# Reefing-PSU.net
KiCad netlist of a schematic drawn in Altium Designer
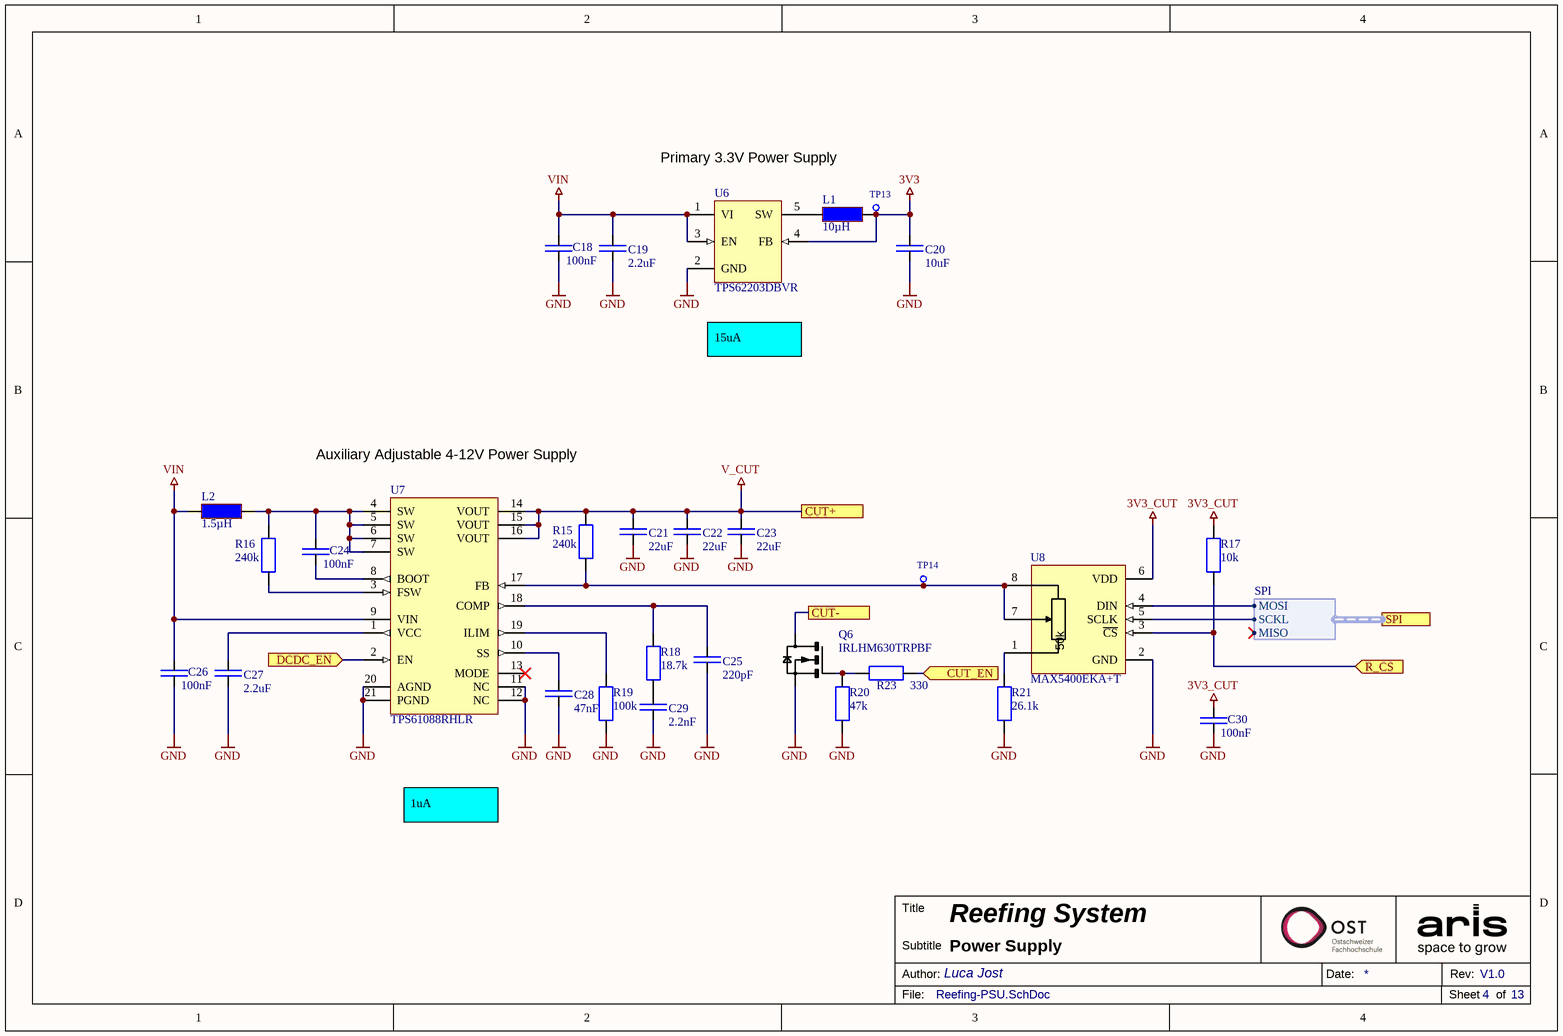
[diagram p0: Reefing-PSU.SchDoc]

(export (version "E")
  (design (tool "Eeschema 10.0.6"))
  (components
    (comp (ref "C18")
      (value "100nF")
      (footprint "SMD Keramikkondensator 0402")
      (description "SMD Ceramic Capacitor E6")
      (libsource (lib "Ceramic Capacitors-E6") (part "E6 - 100nF"))
    )
    (comp (ref "C19")
      (value "2.2uF")
      (footprint "SMD Keramikkondensator 0402")
      (description "SMD Ceramic Capacitor E6")
      (libsource (lib "Ceramic Capacitors-E6") (part "E6 - 2.2uF"))
    )
    (comp (ref "C20")
      (value "10uF")
      (footprint "SMD Keramikkondensator 0603")
      (description "SMD Ceramic Capacitor E6")
      (libsource (lib "Ceramic Capacitors-E6") (part "E6 - 10uF"))
    )
    (comp (ref "C21")
      (value "22uF")
      (footprint "SMD Keramikkondensator 0805")
      (description "SMD Ceramic Capacitor E6")
      (libsource (lib "Ceramic Capacitors-E6") (part "E6 - 22uF"))
    )
    (comp (ref "C22")
      (value "22uF")
      (footprint "SMD Keramikkondensator 0805")
      (description "SMD Ceramic Capacitor E6")
      (libsource (lib "Ceramic Capacitors-E6") (part "E6 - 22uF"))
    )
    (comp (ref "C23")
      (value "22uF")
      (footprint "SMD Keramikkondensator 0805")
      (description "SMD Ceramic Capacitor E6")
      (libsource (lib "Ceramic Capacitors-E6") (part "E6 - 22uF"))
    )
    (comp (ref "C24")
      (value "100nF")
      (footprint "SMD Keramikkondensator 0402")
      (description "SMD Ceramic Capacitor E6")
      (libsource (lib "Ceramic Capacitors-E6") (part "E6 - 100nF"))
    )
    (comp (ref "C25")
      (value "220pF")
      (footprint "SMD Keramikkondensator 0402")
      (description "SMD Ceramic Capacitor E6")
      (libsource (lib "Ceramic Capacitors-E6") (part "E6 - 220pF"))
    )
    (comp (ref "C26")
      (value "100nF")
      (footprint "SMD Keramikkondensator 0402")
      (description "SMD Ceramic Capacitor E6")
      (libsource (lib "Ceramic Capacitors-E6") (part "E6 - 100nF"))
    )
    (comp (ref "C27")
      (value "2.2uF")
      (footprint "SMD Keramikkondensator 0402")
      (description "SMD Ceramic Capacitor E6")
      (libsource (lib "Ceramic Capacitors-E6") (part "E6 - 2.2uF"))
    )
    (comp (ref "C28")
      (value "47nF")
      (footprint "SMD Keramikkondensator 0402")
      (description "SMD Ceramic Capacitor E6")
      (libsource (lib "Ceramic Capacitors-E6") (part "E6 - 47nF"))
    )
    (comp (ref "C29")
      (value "2.2nF")
      (footprint "SMD Keramikkondensator 0402")
      (description "SMD Ceramic Capacitor E6")
      (libsource (lib "Ceramic Capacitors-E6") (part "E6 - 2.2nF"))
    )
    (comp (ref "C30")
      (value "100nF")
      (footprint "SMD Keramikkondensator 0402")
      (description "SMD Ceramic Capacitor E6")
      (libsource (lib "Ceramic Capacitors-E6") (part "E6 - 100nF"))
    )
    (comp (ref "L1")
      (value "10µH")
      (footprint "SMD Inductor 4x4x1.8")
      (description "165mOhm SMD, 1.6A")
      (libsource (lib "Inductors") (part "Inductor 10µH / 1.6A"))
    )
    (comp (ref "L2")
      (value "1.5µH")
      (footprint "SMD Inductor 7.1x6.6")
      (description "8.5mΩ SMD, 7.1x6.6x5mm")
      (libsource (lib "Inductors") (part "Inductor 1.5µH / 10A"))
    )
    (comp (ref "Q6")
      (value "IRLHM630TRPBF")
      (footprint "SMD MOSFET DFN 3.3x3.3")
      (description "N-Channel 30V 21A 3.5mOhm@4.5V")
      (libsource (lib "Reefing System") (part "IRLHM630TRPBF"))
    )
    (comp (ref "R15")
      (value "240k")
      (footprint "SMD Widerstand 0402")
      (description "SMD Chip Resistor E24")
      (libsource (lib "Resistors-E24") (part "E24 - 240k"))
    )
    (comp (ref "R16")
      (value "240k")
      (footprint "SMD Widerstand 0402")
      (description "SMD Chip Resistor E24")
      (libsource (lib "Resistors-E24") (part "E24 - 240k"))
    )
    (comp (ref "R17")
      (value "10k")
      (footprint "SMD Widerstand 0402")
      (description "SMD Chip Resistor E24")
      (libsource (lib "Resistors-E24") (part "E24 - 10k"))
    )
    (comp (ref "R18")
      (value "18.7k")
      (footprint "SMD Widerstand 0402")
      (description "SMD Chip Resistor E96")
      (libsource (lib "Resistors-E96") (part "E96 - 18.7k"))
    )
    (comp (ref "R19")
      (value "100k")
      (footprint "SMD Widerstand 0402")
      (description "SMD Chip Resistor E24")
      (libsource (lib "Resistors-E24") (part "E24 - 100k"))
    )
    (comp (ref "R20")
      (value "47k")
      (footprint "SMD Widerstand 0402")
      (description "SMD Chip Resistor E24")
      (libsource (lib "Resistors-E24") (part "E24 - 47k"))
    )
    (comp (ref "R21")
      (value "26.1k")
      (footprint "SMD Widerstand 0402")
      (description "SMD Chip Resistor E96")
      (libsource (lib "Resistors-E96") (part "E96 - 26.1k"))
    )
    (comp (ref "R23")
      (value "330")
      (footprint "SMD Widerstand 0402")
      (description "SMD Chip Resistor E24")
      (libsource (lib "Resistors-E24") (part "E24 - 330"))
    )
    (comp (ref "TP13")
      (value "X-TP")
      (footprint "SMD Testpoint 1mm")
      (description "Testpunkt")
      (libsource (lib "Fleet-Monitor") (part "X-TP"))
    )
    (comp (ref "TP14")
      (value "X-TP")
      (footprint "SMD Testpoint 1mm")
      (description "Testpunkt")
      (libsource (lib "Fleet-Monitor") (part "X-TP"))
    )
    (comp (ref "U6")
      (value "TPS62203DBVR")
      (footprint "SMD IC SOT-23-5")
      (libsource (lib "Voltage-Converter") (part "TPS62203DBVR"))
    )
    (comp (ref "U7")
      (value "TPS61088RHLR")
      (footprint "SMD IC VQFN-20")
      (description "10-A Fully-Integrated Synchronous Boost Converter")
      (libsource (lib "Voltage-Converter") (part "TPS61088RHLR"))
    )
    (comp (ref "U8")
      (value "MAX5400EKA+T")
      (footprint "SMD IC SOT-23-8")
      (description "Low-Drift Digital Potentiometer")
      (libsource (lib "Analog") (part "MAX5400EKA+T"))
    )
  )
  (nets
    (net (code "2") (name "/CUT-") (class "Default")
      (node (ref "Q6") (pin "D") (pinfunction "D_D") (pintype "passive"))
    )
    (net (code "3") (name "/CUT_EN") (class "Default")
      (node (ref "R23") (pin "1") (pinfunction "1_1") (pintype "passive"))
    )
    (net (code "4") (name "/DCDC_EN") (class "Default")
      (node (ref "U7") (pin "2") (pinfunction "EN_2") (pintype "input"))
    )
    (net (code "5") (name "/MOSI") (class "Default")
      (node (ref "U8") (pin "4") (pinfunction "DIN_4") (pintype "input"))
    )
    (net (code "6") (name "/R_CS") (class "Default")
      (node (ref "R17") (pin "1") (pinfunction "1_1") (pintype "passive"))
      (node (ref "U8") (pin "3") (pinfunction "~{CS}_3") (pintype "input"))
    )
    (net (code "7") (name "/SCKL") (class "Default")
      (node (ref "U8") (pin "5") (pinfunction "SCLK_5") (pintype "input"))
    )
    (net (code "9") (name "3V3") (class "Default")
      (node (ref "C20") (pin "2") (pinfunction "2_2") (pintype "passive"))
      (node (ref "L1") (pin "2") (pinfunction "2_2") (pintype "passive"))
      (node (ref "TP13") (pin "1") (pinfunction "1_1") (pintype "passive"))
      (node (ref "U6") (pin "4") (pinfunction "FB_4") (pintype "input"))
    )
    (net (code "10") (name "3V3_CUT") (class "Default")
      (node (ref "C30") (pin "2") (pinfunction "2_2") (pintype "passive"))
      (node (ref "R17") (pin "2") (pinfunction "2_2") (pintype "passive"))
      (node (ref "U8") (pin "6") (pinfunction "VDD_6") (pintype "passive"))
    )
    (net (code "11") (name "GND") (class "Default")
      (node (ref "C18") (pin "1") (pinfunction "1_1") (pintype "passive"))
      (node (ref "C19") (pin "1") (pinfunction "1_1") (pintype "passive"))
      (node (ref "C20") (pin "1") (pinfunction "1_1") (pintype "passive"))
      (node (ref "C21") (pin "1") (pinfunction "1_1") (pintype "passive"))
      (node (ref "C22") (pin "1") (pinfunction "1_1") (pintype "passive"))
      (node (ref "C23") (pin "1") (pinfunction "1_1") (pintype "passive"))
      (node (ref "C25") (pin "1") (pinfunction "1_1") (pintype "passive"))
      (node (ref "C26") (pin "1") (pinfunction "1_1") (pintype "passive"))
      (node (ref "C27") (pin "1") (pinfunction "1_1") (pintype "passive"))
      (node (ref "C28") (pin "1") (pinfunction "1_1") (pintype "passive"))
      (node (ref "C29") (pin "1") (pinfunction "1_1") (pintype "passive"))
      (node (ref "C30") (pin "1") (pinfunction "1_1") (pintype "passive"))
      (node (ref "Q6") (pin "S") (pinfunction "S_S") (pintype "passive"))
      (node (ref "R19") (pin "1") (pinfunction "1_1") (pintype "passive"))
      (node (ref "R20") (pin "1") (pinfunction "1_1") (pintype "passive"))
      (node (ref "R21") (pin "1") (pinfunction "1_1") (pintype "passive"))
      (node (ref "U6") (pin "2") (pinfunction "GND_2") (pintype "passive"))
      (node (ref "U7") (pin "11") (pinfunction "NC_11") (pintype "passive"))
      (node (ref "U7") (pin "12") (pinfunction "NC_12") (pintype "passive"))
      (node (ref "U7") (pin "20") (pinfunction "AGND_20") (pintype "passive"))
      (node (ref "U7") (pin "21") (pinfunction "PGND_21") (pintype "passive"))
      (node (ref "U8") (pin "2") (pinfunction "GND_2") (pintype "passive"))
    )
    (net (code "12") (name "Net-(C24-Pad2)") (class "Default")
      (node (ref "C24") (pin "2") (pinfunction "2_2") (pintype "passive"))
      (node (ref "L2") (pin "2") (pinfunction "2_2") (pintype "passive"))
      (node (ref "R16") (pin "2") (pinfunction "2_2") (pintype "passive"))
      (node (ref "U7") (pin "4") (pinfunction "SW_4") (pintype "passive"))
      (node (ref "U7") (pin "5") (pinfunction "SW_5") (pintype "passive"))
      (node (ref "U7") (pin "6") (pinfunction "SW_6") (pintype "passive"))
      (node (ref "U7") (pin "7") (pinfunction "SW_7") (pintype "passive"))
    )
    (net (code "13") (name "Net-(C29-Pad2)") (class "Default")
      (node (ref "C29") (pin "2") (pinfunction "2_2") (pintype "passive"))
      (node (ref "R18") (pin "1") (pinfunction "1_1") (pintype "passive"))
    )
    (net (code "14") (name "Net-(Q6-PadG)") (class "Default")
      (node (ref "Q6") (pin "G") (pinfunction "G_G") (pintype "passive"))
      (node (ref "R20") (pin "2") (pinfunction "2_2") (pintype "passive"))
      (node (ref "R23") (pin "2") (pinfunction "2_2") (pintype "passive"))
    )
    (net (code "15") (name "Net-(U6-SW)") (class "Default")
      (node (ref "L1") (pin "1") (pinfunction "1_1") (pintype "passive"))
      (node (ref "U6") (pin "5") (pinfunction "SW_5") (pintype "passive"))
    )
    (net (code "16") (name "Net-(U7-BOOT)") (class "Default")
      (node (ref "C24") (pin "1") (pinfunction "1_1") (pintype "passive"))
      (node (ref "U7") (pin "8") (pinfunction "BOOT_8") (pintype "output"))
    )
    (net (code "17") (name "Net-(U7-COMP)") (class "Default")
      (node (ref "C25") (pin "2") (pinfunction "2_2") (pintype "passive"))
      (node (ref "R18") (pin "2") (pinfunction "2_2") (pintype "passive"))
      (node (ref "U7") (pin "18") (pinfunction "COMP_18") (pintype "output"))
    )
    (net (code "18") (name "Net-(U7-FB)") (class "Default")
      (node (ref "R15") (pin "1") (pinfunction "1_1") (pintype "passive"))
      (node (ref "TP14") (pin "1") (pinfunction "1_1") (pintype "passive"))
      (node (ref "U7") (pin "17") (pinfunction "FB_17") (pintype "input"))
      (node (ref "U8") (pin "7") (pinfunction "W_7") (pintype "passive"))
      (node (ref "U8") (pin "8") (pinfunction "H_8") (pintype "passive"))
    )
    (net (code "19") (name "Net-(U7-FSW)") (class "Default")
      (node (ref "R16") (pin "1") (pinfunction "1_1") (pintype "passive"))
      (node (ref "U7") (pin "3") (pinfunction "FSW_3") (pintype "input"))
    )
    (net (code "20") (name "Net-(U7-ILIM)") (class "Default")
      (node (ref "R19") (pin "2") (pinfunction "2_2") (pintype "passive"))
      (node (ref "U7") (pin "19") (pinfunction "ILIM_19") (pintype "output"))
    )
    (net (code "21") (name "Net-(U7-SS)") (class "Default")
      (node (ref "C28") (pin "2") (pinfunction "2_2") (pintype "passive"))
      (node (ref "U7") (pin "10") (pinfunction "SS_10") (pintype "output"))
    )
    (net (code "22") (name "Net-(U7-VCC)") (class "Default")
      (node (ref "C27") (pin "2") (pinfunction "2_2") (pintype "passive"))
      (node (ref "U7") (pin "1") (pinfunction "VCC_1") (pintype "output"))
    )
    (net (code "23") (name "Net-(U8-L)") (class "Default")
      (node (ref "R21") (pin "2") (pinfunction "2_2") (pintype "passive"))
      (node (ref "U8") (pin "1") (pinfunction "L_1") (pintype "passive"))
    )
    (net (code "24") (name "VIN") (class "Default")
      (node (ref "C18") (pin "2") (pinfunction "2_2") (pintype "passive"))
      (node (ref "C19") (pin "2") (pinfunction "2_2") (pintype "passive"))
      (node (ref "C26") (pin "2") (pinfunction "2_2") (pintype "passive"))
      (node (ref "L2") (pin "1") (pinfunction "1_1") (pintype "passive"))
      (node (ref "U6") (pin "1") (pinfunction "VI_1") (pintype "passive"))
      (node (ref "U6") (pin "3") (pinfunction "EN_3") (pintype "input"))
      (node (ref "U7") (pin "9") (pinfunction "VIN_9") (pintype "passive"))
    )
    (net (code "25") (name "V_CUT") (class "Default")
      (node (ref "C21") (pin "2") (pinfunction "2_2") (pintype "passive"))
      (node (ref "C22") (pin "2") (pinfunction "2_2") (pintype "passive"))
      (node (ref "C23") (pin "2") (pinfunction "2_2") (pintype "passive"))
      (node (ref "R15") (pin "2") (pinfunction "2_2") (pintype "passive"))
      (node (ref "U7") (pin "14") (pinfunction "VOUT_14") (pintype "passive"))
      (node (ref "U7") (pin "15") (pinfunction "VOUT_15") (pintype "passive"))
      (node (ref "U7") (pin "16") (pinfunction "VOUT_16") (pintype "passive"))
    )
    (net (code "26") (name "unconnected-(U7-MODE-Pad13)") (class "Default")
      (node (ref "U7") (pin "13") (pinfunction "MODE_13") (pintype "passive+no_connect"))
    )
  )
)
